# WiFi_UART_Board_R1_0_1.net
KiCad netlist of a schematic drawn in EAGLE
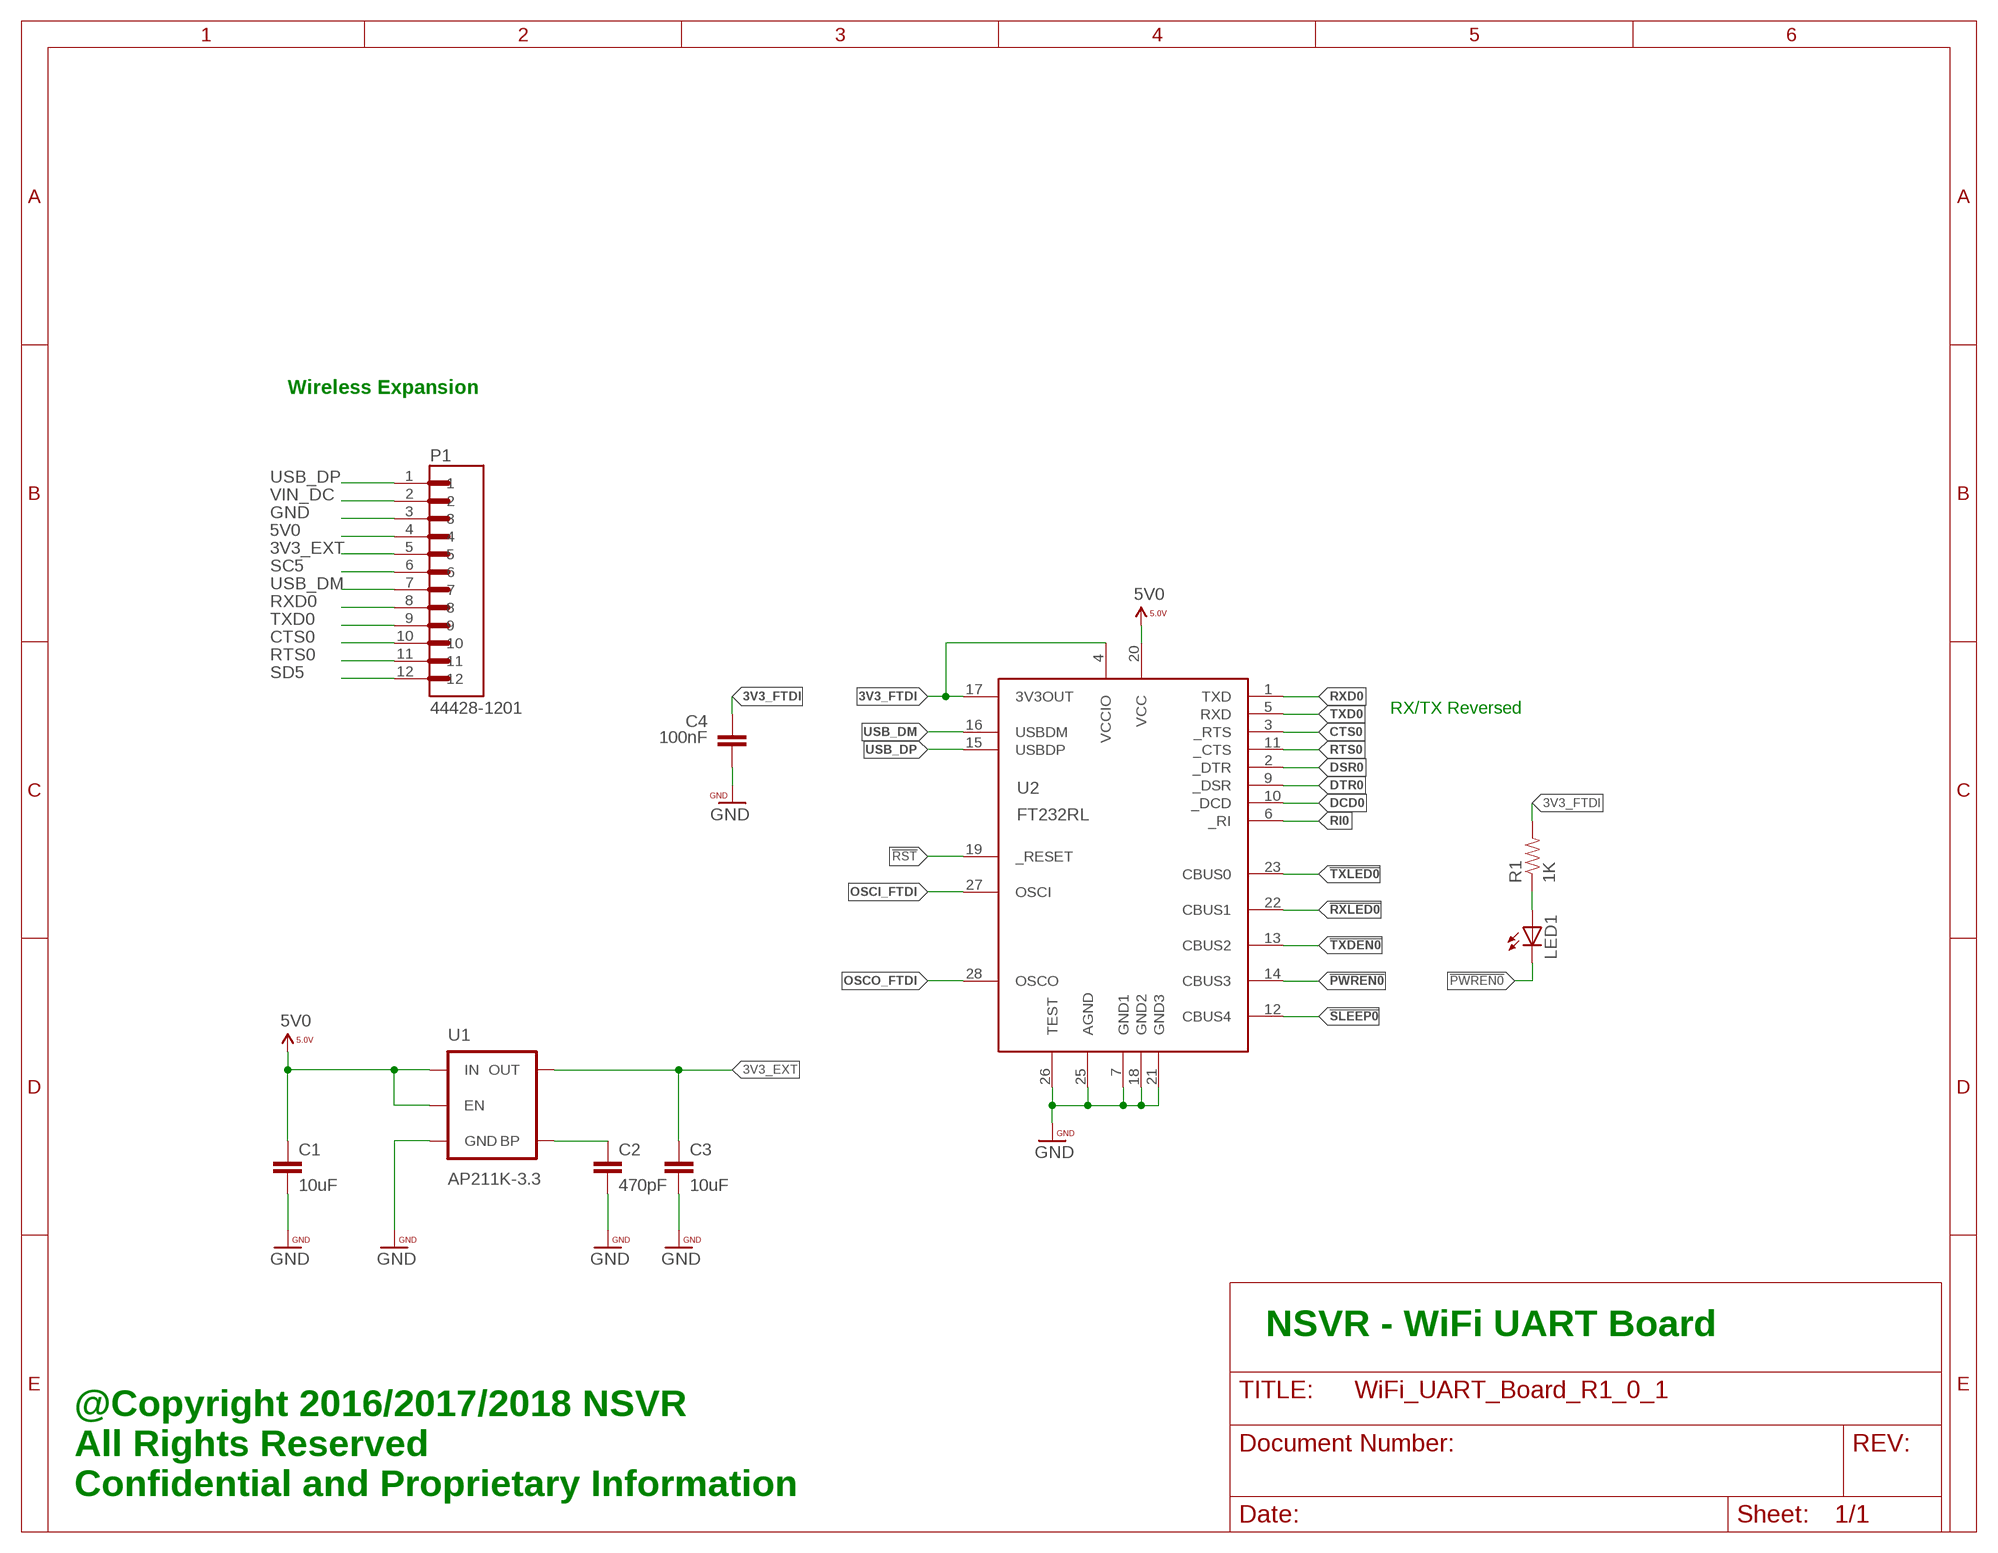
[diagram p0: schematic, sheet 1]

(export (version "E")
  (design (tool "Eeschema 10.0.6"))
  (components
    (comp (ref "C1")
      (value "10uF")
      (footprint "eagle-import:0603-CAP")
      (libsource (lib "eagle-import") (part "CAP0603-CAP"))
    )
    (comp (ref "C2")
      (value "470pF")
      (footprint "eagle-import:0402-CAP")
      (libsource (lib "eagle-import") (part "CAP0402-CAP"))
    )
    (comp (ref "C3")
      (value "10uF")
      (footprint "eagle-import:0603-CAP")
      (libsource (lib "eagle-import") (part "CAP0603-CAP"))
    )
    (comp (ref "C4")
      (value "100nF")
      (footprint "eagle-import:0402-CAP")
      (libsource (lib "eagle-import") (part "CAP0402-CAP"))
    )
    (comp (ref "LED1")
      (value "LEDCHIP-LED0603")
      (footprint "eagle-import:CHIP-LED0603")
      (libsource (lib "eagle-import") (part "LEDCHIP-LED0603"))
    )
    (comp (ref "P1")
      (value "44428-1201")
      (footprint "eagle-import:MOLEX_44428-1201")
      (fields (field (name "MF") "Molex"))
      (libsource (lib "eagle-import") (part "44428-1201"))
    )
    (comp (ref "R1")
      (value "1K")
      (footprint "eagle-import:EIA-0402")
      (libsource (lib "eagle-import") (part "RESISTOR0402-TYP"))
    )
    (comp (ref "U1")
      (value "AP211K-3.3")
      (footprint "eagle-import:SOT23-5")
      (libsource (lib "eagle-import") (part "V_REG_MIC52053.3V"))
    )
    (comp (ref "U2")
      (value "FT232RL")
      (footprint "eagle-import:SSOP28DB")
      (libsource (lib "eagle-import") (part "FT232RL"))
    )
  )
  (nets
    (net (code "1") (name "/SC5") (class "Default")
      (node (ref "P1") (pin "6") (pinfunction "6_6") (pintype "passive"))
    )
    (net (code "2") (name "/SD5") (class "Default")
      (node (ref "P1") (pin "12") (pinfunction "12_12") (pintype "passive"))
    )
    (net (code "3") (name "/VIN_DC") (class "Default")
      (node (ref "P1") (pin "2") (pinfunction "2_2") (pintype "passive"))
    )
    (net (code "4") (name "/~{PWREN0}") (class "Default")
      (node (ref "LED1") (pin "C") (pinfunction "C_C") (pintype "passive"))
      (node (ref "U2") (pin "14") (pinfunction "CBUS3_14") (pintype "bidirectional"))
    )
    (net (code "5") (name "/~{RST}") (class "Default")
      (node (ref "U2") (pin "19") (pinfunction "_RESET_19") (pintype "input"))
    )
    (net (code "6") (name "/~{RXLED0}") (class "Default")
      (node (ref "U2") (pin "22") (pinfunction "CBUS1_22") (pintype "bidirectional"))
    )
    (net (code "7") (name "/~{SLEEP0}") (class "Default")
      (node (ref "U2") (pin "12") (pinfunction "CBUS4_12") (pintype "bidirectional"))
    )
    (net (code "8") (name "/~{TXDEN0}") (class "Default")
      (node (ref "U2") (pin "13") (pinfunction "CBUS2_13") (pintype "bidirectional"))
    )
    (net (code "9") (name "/~{TXLED0}") (class "Default")
      (node (ref "U2") (pin "23") (pinfunction "CBUS0_23") (pintype "bidirectional"))
    )
    (net (code "10") (name "3V3_EXT") (class "Default")
      (node (ref "C3") (pin "1") (pinfunction "1_1") (pintype "passive"))
      (node (ref "P1") (pin "5") (pinfunction "5_5") (pintype "passive"))
      (node (ref "U1") (pin "5") (pinfunction "OUT_5") (pintype "passive"))
    )
    (net (code "11") (name "3V3_FTDI") (class "Default")
      (node (ref "C4") (pin "1") (pinfunction "1_1") (pintype "passive"))
      (node (ref "R1") (pin "2") (pinfunction "2_2") (pintype "passive"))
      (node (ref "U2") (pin "17") (pinfunction "3V3OUT_17") (pintype "output"))
      (node (ref "U2") (pin "4") (pinfunction "VCCIO_4") (pintype "power_in"))
    )
    (net (code "12") (name "5V0") (class "Default")
      (node (ref "C1") (pin "1") (pinfunction "1_1") (pintype "passive"))
      (node (ref "P1") (pin "4") (pinfunction "4_4") (pintype "passive"))
      (node (ref "U1") (pin "1") (pinfunction "IN_1") (pintype "input"))
      (node (ref "U1") (pin "3") (pinfunction "EN_3") (pintype "input"))
      (node (ref "U2") (pin "20") (pinfunction "VCC_20") (pintype "power_in"))
    )
    (net (code "13") (name "CTS0") (class "Default")
      (node (ref "P1") (pin "10") (pinfunction "10_10") (pintype "passive"))
      (node (ref "U2") (pin "3") (pinfunction "_RTS_3") (pintype "output"))
    )
    (net (code "14") (name "DCD0") (class "Default")
      (node (ref "U2") (pin "10") (pinfunction "_DCD_10") (pintype "input"))
    )
    (net (code "15") (name "DSR0") (class "Default")
      (node (ref "U2") (pin "2") (pinfunction "_DTR_2") (pintype "output"))
    )
    (net (code "16") (name "DTR0") (class "Default")
      (node (ref "U2") (pin "9") (pinfunction "_DSR_9") (pintype "input"))
    )
    (net (code "17") (name "GND") (class "Default")
      (node (ref "C1") (pin "2") (pinfunction "2_2") (pintype "passive"))
      (node (ref "C2") (pin "2") (pinfunction "2_2") (pintype "passive"))
      (node (ref "C3") (pin "2") (pinfunction "2_2") (pintype "passive"))
      (node (ref "C4") (pin "2") (pinfunction "2_2") (pintype "passive"))
      (node (ref "P1") (pin "3") (pinfunction "3_3") (pintype "passive"))
      (node (ref "U1") (pin "2") (pinfunction "GND_2") (pintype "input"))
      (node (ref "U2") (pin "18") (pinfunction "GND2_18") (pintype "power_in"))
      (node (ref "U2") (pin "21") (pinfunction "GND3_21") (pintype "power_in"))
      (node (ref "U2") (pin "25") (pinfunction "AGND_25") (pintype "power_in"))
      (node (ref "U2") (pin "26") (pinfunction "TEST_26") (pintype "input"))
      (node (ref "U2") (pin "7") (pinfunction "GND1_7") (pintype "power_in"))
    )
    (net (code "18") (name "Net-(LED1-PadA)") (class "Default")
      (node (ref "LED1") (pin "A") (pinfunction "A_A") (pintype "passive"))
      (node (ref "R1") (pin "1") (pinfunction "1_1") (pintype "passive"))
    )
    (net (code "19") (name "Net-(U1-BP)") (class "Default")
      (node (ref "C2") (pin "1") (pinfunction "1_1") (pintype "passive"))
      (node (ref "U1") (pin "4") (pinfunction "BP_4") (pintype "input"))
    )
    (net (code "20") (name "OSCI_FTDI") (class "Default")
      (node (ref "U2") (pin "27") (pinfunction "OSCI_27") (pintype "input"))
    )
    (net (code "21") (name "OSCO_FTDI") (class "Default")
      (node (ref "U2") (pin "28") (pinfunction "OSCO_28") (pintype "output"))
    )
    (net (code "22") (name "RI0") (class "Default")
      (node (ref "U2") (pin "6") (pinfunction "_RI_6") (pintype "input"))
    )
    (net (code "23") (name "RTS0") (class "Default")
      (node (ref "P1") (pin "11") (pinfunction "11_11") (pintype "passive"))
      (node (ref "U2") (pin "11") (pinfunction "_CTS_11") (pintype "input"))
    )
    (net (code "24") (name "RXD0") (class "Default")
      (node (ref "P1") (pin "8") (pinfunction "8_8") (pintype "passive"))
      (node (ref "U2") (pin "1") (pinfunction "TXD_1") (pintype "output"))
    )
    (net (code "25") (name "TXD0") (class "Default")
      (node (ref "P1") (pin "9") (pinfunction "9_9") (pintype "passive"))
      (node (ref "U2") (pin "5") (pinfunction "RXD_5") (pintype "input"))
    )
    (net (code "26") (name "USB_DM") (class "Default")
      (node (ref "P1") (pin "7") (pinfunction "7_7") (pintype "passive"))
      (node (ref "U2") (pin "16") (pinfunction "USBDM_16") (pintype "bidirectional"))
    )
    (net (code "27") (name "USB_DP") (class "Default")
      (node (ref "P1") (pin "1") (pinfunction "1_1") (pintype "passive"))
      (node (ref "U2") (pin "15") (pinfunction "USBDP_15") (pintype "bidirectional"))
    )
  )
)
